# CPU_LPDDR4.net
KiCad netlist of a schematic drawn in Altium Designer
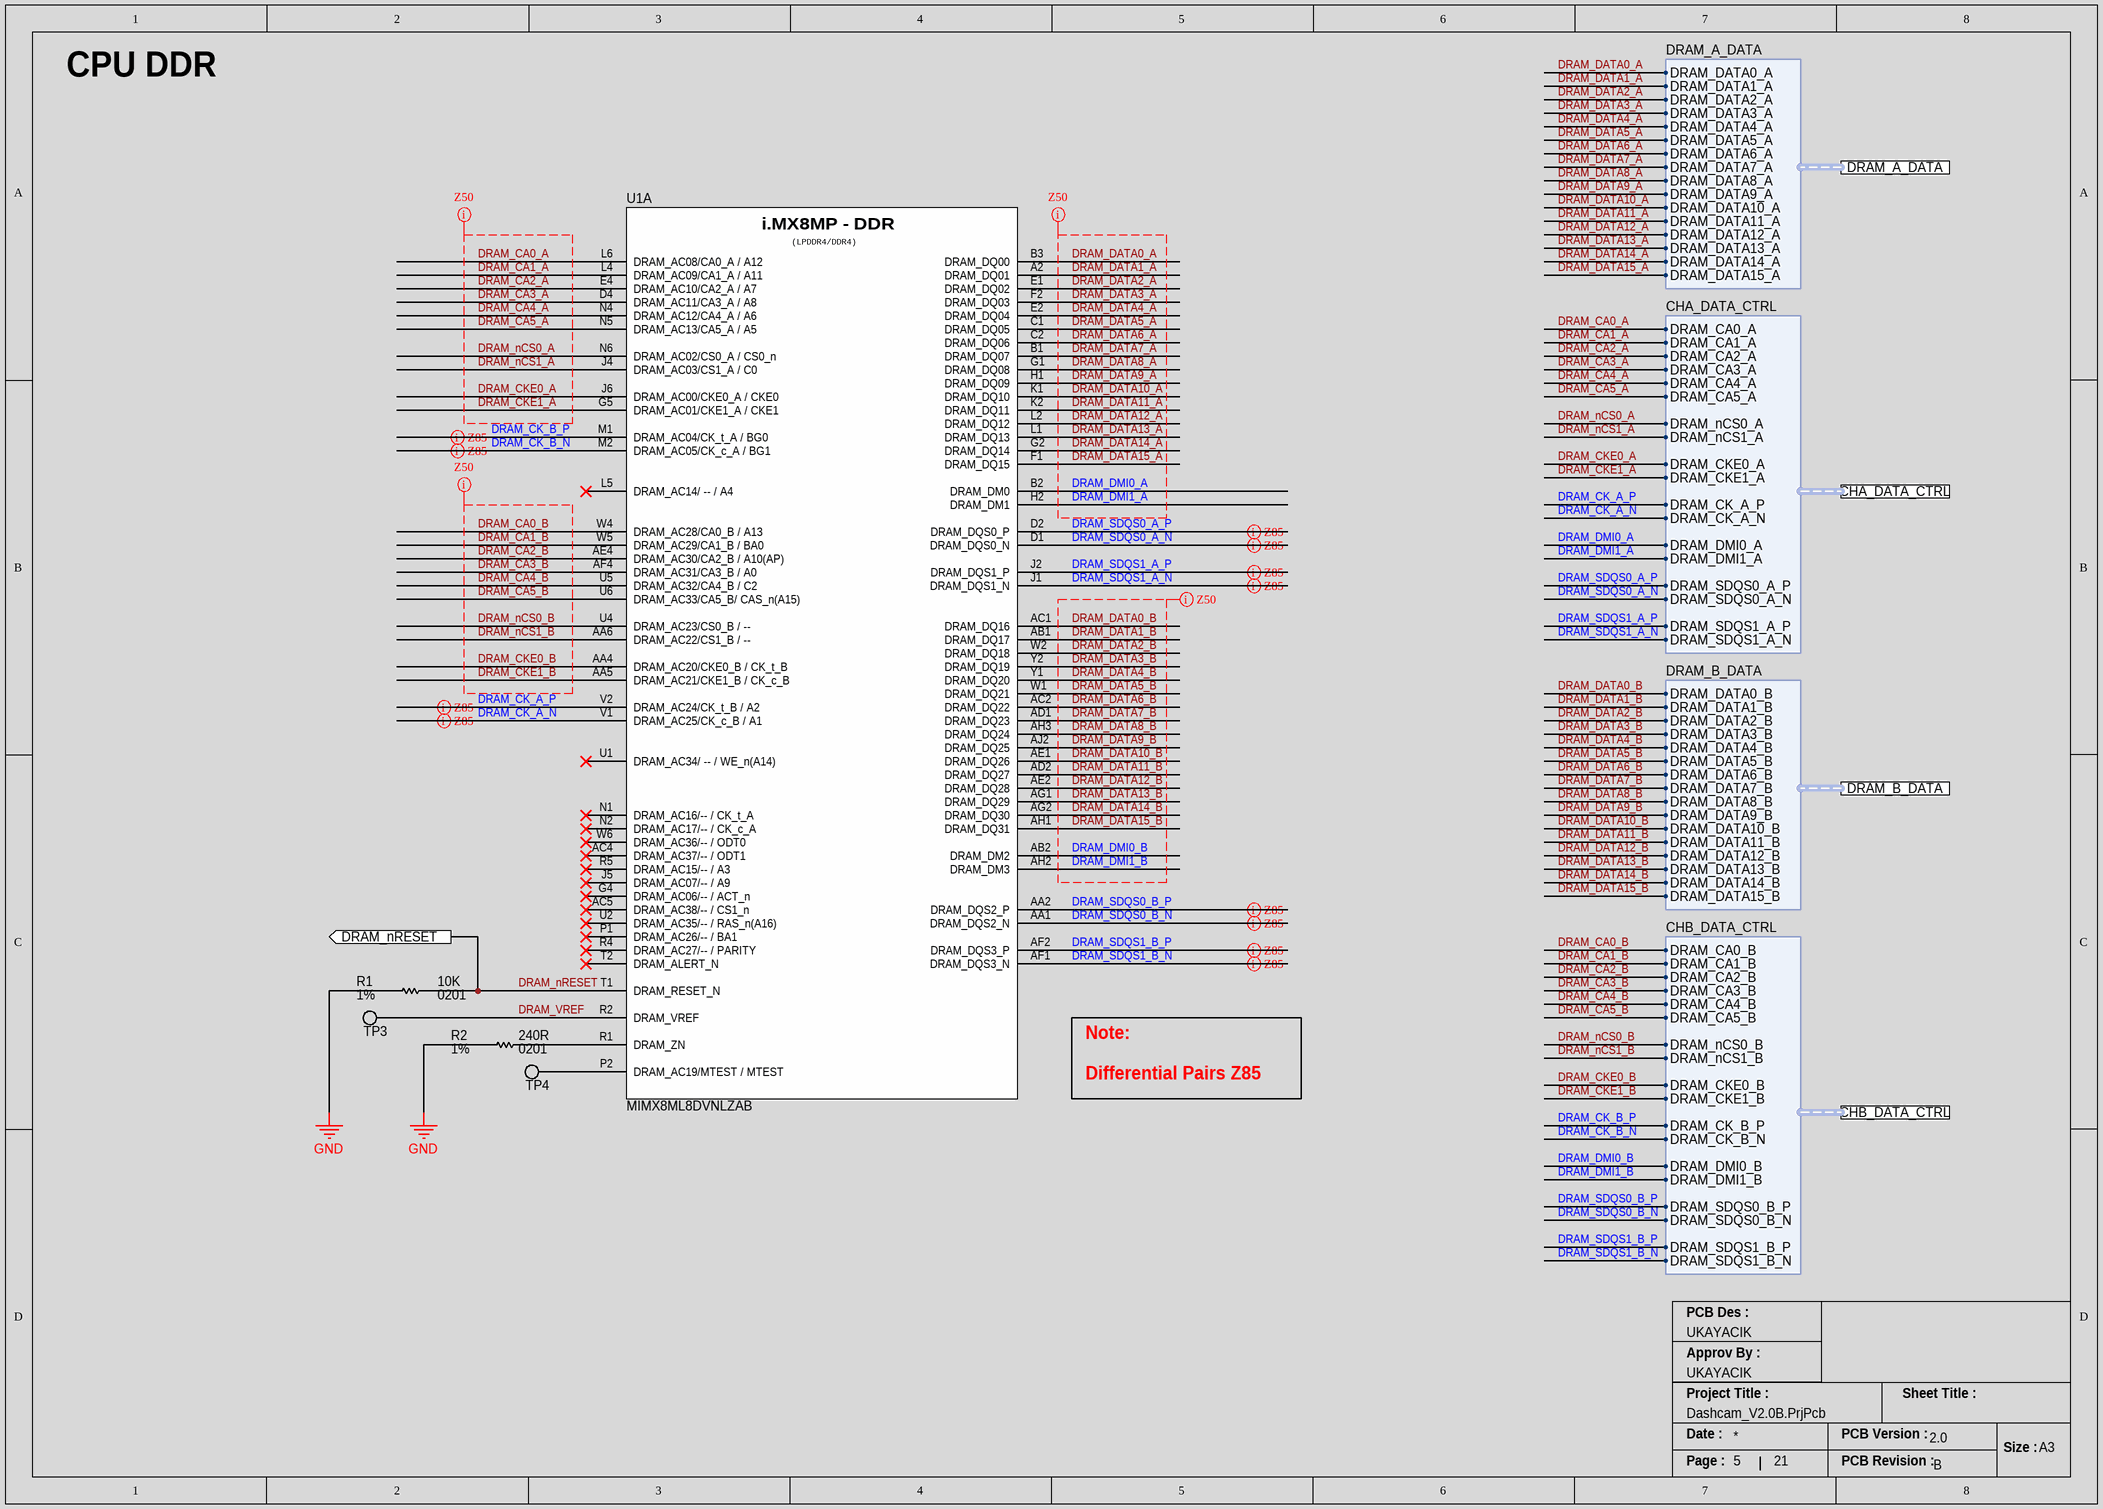
[diagram p0: CPU LPDDR4.SchDoc]

(export (version "E")
  (design (tool "Eeschema 10.0.6"))
  (components
    (comp (ref "R1")
      (value "RC0201FR-0710KL")
      (footprint "RES_0201_RESC0603X02N")
      (description "SMD Chip Resistor, 10 kOhm, ± 1%, 50 mW, 0201 [0603 Metric], Thick Film, General Purpose")
      (fields
        (field (name "MANUFACTURER") "Yageo")
        (field (name "TOLERANCE") "1%")
        (field (name "RESISTANCE") "10K")
        (field (name "CASE CODE (IMPERIAL)") "0201")
      )
      (libsource (lib "Electronic Devices_LIB") (part "RES_10K_1/12W_1%_0201"))
    )
    (comp (ref "R2")
      (value "RC0201FR-07240RL")
      (footprint "RES_0201_RESC0603X02N")
      (description "SMD Chip Resistor, 240 Ohm, ± 1%, 50 mW, 0201 [0603 Metric], Thick Film, General Purpose")
      (fields
        (field (name "MANUFACTURER") "Yageo")
        (field (name "TOLERANCE") "1%")
        (field (name "RESISTANCE") "240R")
        (field (name "CASE/PACKAGE") "0201")
      )
      (libsource (lib "Electronic Devices_LIB") (part "RES_240R_1%_50mW_0201"))
    )
    (comp (ref "TP3")
      (value "NO COMPONENT")
      (footprint "TP_PAD_0.5MM_SMD_ROUND")
      (description "Test Point, SMD pad, round, 1.5mm, 1.6mm, 3mm diameter")
      (libsource (lib "Electronic Devices_LIB") (part "TP_PAD_SMD_SMALL"))
    )
    (comp (ref "TP4")
      (value "NO COMPONENT")
      (footprint "TP_PAD_0.5MM_SMD_ROUND")
      (description "Test Point, SMD pad, round, 1.5mm, 1.6mm, 3mm diameter")
      (libsource (lib "Electronic Devices_LIB") (part "TP_PAD_SMD_SMALL"))
    )
    (comp (ref "U1")
      (value "MIMX8ML8DVNLZAB")
      (footprint "IC_MPU_BGA548C50P29X29_1500X1500X148")
      (description "i.MX 8M Plus, Consumer, / TRAY TRAY MULTIPLE DP BAKEABLE RoHS Compliant: Yes")
      (fields (field (name "MANUFACTURER") "NXP Semiconductors"))
      (libsource (lib "Electronic Devices_LIB") (part "IC_MPU_8M_PLUS_MIMX8ML8DVNLZAB"))
    )
  )
  (nets
    (net (code "5") (name "/DRAM_CA0_A") (class "Default")
      (node (ref "U1") (pin "L6") (pinfunction "DRAM_AC08/CA0_A_/_A12_L6") (pintype "passive"))
    )
    (net (code "6") (name "/DRAM_CA0_B") (class "Default")
      (node (ref "U1") (pin "W4") (pinfunction "DRAM_AC28/CA0_B_/_A13_W4") (pintype "passive"))
    )
    (net (code "7") (name "/DRAM_CA1_A") (class "Default")
      (node (ref "U1") (pin "L4") (pinfunction "DRAM_AC09/CA1_A_/_A11_L4") (pintype "passive"))
    )
    (net (code "8") (name "/DRAM_CA1_B") (class "Default")
      (node (ref "U1") (pin "W5") (pinfunction "DRAM_AC29/CA1_B_/_BA0_W5") (pintype "passive"))
    )
    (net (code "9") (name "/DRAM_CA2_A") (class "Default")
      (node (ref "U1") (pin "E4") (pinfunction "DRAM_AC10/CA2_A_/_A7_E4") (pintype "passive"))
    )
    (net (code "10") (name "/DRAM_CA2_B") (class "Default")
      (node (ref "U1") (pin "AE4") (pinfunction "DRAM_AC30/CA2_B_/_A10(AP)_AE4") (pintype "passive"))
    )
    (net (code "11") (name "/DRAM_CA3_A") (class "Default")
      (node (ref "U1") (pin "D4") (pinfunction "DRAM_AC11/CA3_A_/_A8_D4") (pintype "passive"))
    )
    (net (code "12") (name "/DRAM_CA3_B") (class "Default")
      (node (ref "U1") (pin "AF4") (pinfunction "DRAM_AC31/CA3_B_/_A0_AF4") (pintype "passive"))
    )
    (net (code "13") (name "/DRAM_CA4_A") (class "Default")
      (node (ref "U1") (pin "N4") (pinfunction "DRAM_AC12/CA4_A_/_A6_N4") (pintype "passive"))
    )
    (net (code "14") (name "/DRAM_CA4_B") (class "Default")
      (node (ref "U1") (pin "U5") (pinfunction "DRAM_AC32/CA4_B_/_C2_U5") (pintype "passive"))
    )
    (net (code "15") (name "/DRAM_CA5_A") (class "Default")
      (node (ref "U1") (pin "N5") (pinfunction "DRAM_AC13/CA5_A_/_A5_N5") (pintype "passive"))
    )
    (net (code "16") (name "/DRAM_CA5_B") (class "Default")
      (node (ref "U1") (pin "U6") (pinfunction "DRAM_AC33/CA5_B/_CAS_n(A15)_U6") (pintype "passive"))
    )
    (net (code "17") (name "/DRAM_CKE0_A") (class "Default")
      (node (ref "U1") (pin "J6") (pinfunction "DRAM_AC00/CKE0_A_/_CKE0_J6") (pintype "passive"))
    )
    (net (code "18") (name "/DRAM_CKE0_B") (class "Default")
      (node (ref "U1") (pin "AA4") (pinfunction "DRAM_AC20/CKE0_B_/_CK_t_B_AA4") (pintype "passive"))
    )
    (net (code "19") (name "/DRAM_CKE1_A") (class "Default")
      (node (ref "U1") (pin "G5") (pinfunction "DRAM_AC01/CKE1_A_/_CKE1_G5") (pintype "passive"))
    )
    (net (code "20") (name "/DRAM_CKE1_B") (class "Default")
      (node (ref "U1") (pin "AA5") (pinfunction "DRAM_AC21/CKE1_B_/_CK_c_B_AA5") (pintype "passive"))
    )
    (net (code "21") (name "/DRAM_CK_A_N") (class "Default")
      (node (ref "U1") (pin "V1") (pinfunction "DRAM_AC25/CK_c_B_/_A1_V1") (pintype "passive"))
    )
    (net (code "22") (name "/DRAM_CK_A_P") (class "Default")
      (node (ref "U1") (pin "V2") (pinfunction "DRAM_AC24/CK_t_B_/_A2_V2") (pintype "passive"))
    )
    (net (code "23") (name "/DRAM_CK_B_N") (class "Default")
      (node (ref "U1") (pin "M2") (pinfunction "DRAM_AC05/CK_c_A_/_BG1_M2") (pintype "passive"))
    )
    (net (code "24") (name "/DRAM_CK_B_P") (class "Default")
      (node (ref "U1") (pin "M1") (pinfunction "DRAM_AC04/CK_t_A_/_BG0_M1") (pintype "passive"))
    )
    (net (code "25") (name "/DRAM_DATA0_A") (class "Default")
      (node (ref "U1") (pin "B3") (pinfunction "DRAM_DQ00_B3") (pintype "passive"))
    )
    (net (code "26") (name "/DRAM_DATA0_B") (class "Default")
      (node (ref "U1") (pin "AC1") (pinfunction "DRAM_DQ16_AC1") (pintype "passive"))
    )
    (net (code "27") (name "/DRAM_DATA1_A") (class "Default")
      (node (ref "U1") (pin "A2") (pinfunction "DRAM_DQ01_A2") (pintype "passive"))
    )
    (net (code "28") (name "/DRAM_DATA1_B") (class "Default")
      (node (ref "U1") (pin "AB1") (pinfunction "DRAM_DQ17_AB1") (pintype "passive"))
    )
    (net (code "29") (name "/DRAM_DATA2_A") (class "Default")
      (node (ref "U1") (pin "E1") (pinfunction "DRAM_DQ02_E1") (pintype "passive"))
    )
    (net (code "30") (name "/DRAM_DATA2_B") (class "Default")
      (node (ref "U1") (pin "W2") (pinfunction "DRAM_DQ18_W2") (pintype "passive"))
    )
    (net (code "31") (name "/DRAM_DATA3_A") (class "Default")
      (node (ref "U1") (pin "F2") (pinfunction "DRAM_DQ03_F2") (pintype "passive"))
    )
    (net (code "32") (name "/DRAM_DATA3_B") (class "Default")
      (node (ref "U1") (pin "Y2") (pinfunction "DRAM_DQ19_Y2") (pintype "passive"))
    )
    (net (code "33") (name "/DRAM_DATA4_A") (class "Default")
      (node (ref "U1") (pin "E2") (pinfunction "DRAM_DQ04_E2") (pintype "passive"))
    )
    (net (code "34") (name "/DRAM_DATA4_B") (class "Default")
      (node (ref "U1") (pin "Y1") (pinfunction "DRAM_DQ20_Y1") (pintype "passive"))
    )
    (net (code "35") (name "/DRAM_DATA5_A") (class "Default")
      (node (ref "U1") (pin "C1") (pinfunction "DRAM_DQ05_C1") (pintype "passive"))
    )
    (net (code "36") (name "/DRAM_DATA5_B") (class "Default")
      (node (ref "U1") (pin "W1") (pinfunction "DRAM_DQ21_W1") (pintype "passive"))
    )
    (net (code "37") (name "/DRAM_DATA6_A") (class "Default")
      (node (ref "U1") (pin "C2") (pinfunction "DRAM_DQ06_C2") (pintype "passive"))
    )
    (net (code "38") (name "/DRAM_DATA6_B") (class "Default")
      (node (ref "U1") (pin "AC2") (pinfunction "DRAM_DQ22_AC2") (pintype "passive"))
    )
    (net (code "39") (name "/DRAM_DATA7_A") (class "Default")
      (node (ref "U1") (pin "B1") (pinfunction "DRAM_DQ07_B1") (pintype "passive"))
    )
    (net (code "40") (name "/DRAM_DATA7_B") (class "Default")
      (node (ref "U1") (pin "AD1") (pinfunction "DRAM_DQ23_AD1") (pintype "passive"))
    )
    (net (code "41") (name "/DRAM_DATA8_A") (class "Default")
      (node (ref "U1") (pin "G1") (pinfunction "DRAM_DQ08_G1") (pintype "passive"))
    )
    (net (code "42") (name "/DRAM_DATA8_B") (class "Default")
      (node (ref "U1") (pin "AH3") (pinfunction "DRAM_DQ24_AH3") (pintype "passive"))
    )
    (net (code "43") (name "/DRAM_DATA9_A") (class "Default")
      (node (ref "U1") (pin "H1") (pinfunction "DRAM_DQ09_H1") (pintype "passive"))
    )
    (net (code "44") (name "/DRAM_DATA9_B") (class "Default")
      (node (ref "U1") (pin "AJ2") (pinfunction "DRAM_DQ25_AJ2") (pintype "passive"))
    )
    (net (code "45") (name "/DRAM_DATA10_A") (class "Default")
      (node (ref "U1") (pin "K1") (pinfunction "DRAM_DQ10_K1") (pintype "passive"))
    )
    (net (code "46") (name "/DRAM_DATA10_B") (class "Default")
      (node (ref "U1") (pin "AE1") (pinfunction "DRAM_DQ26_AE1") (pintype "passive"))
    )
    (net (code "47") (name "/DRAM_DATA11_A") (class "Default")
      (node (ref "U1") (pin "K2") (pinfunction "DRAM_DQ11_K2") (pintype "passive"))
    )
    (net (code "48") (name "/DRAM_DATA11_B") (class "Default")
      (node (ref "U1") (pin "AD2") (pinfunction "DRAM_DQ27_AD2") (pintype "passive"))
    )
    (net (code "49") (name "/DRAM_DATA12_A") (class "Default")
      (node (ref "U1") (pin "L2") (pinfunction "DRAM_DQ12_L2") (pintype "passive"))
    )
    (net (code "50") (name "/DRAM_DATA12_B") (class "Default")
      (node (ref "U1") (pin "AE2") (pinfunction "DRAM_DQ28_AE2") (pintype "passive"))
    )
    (net (code "51") (name "/DRAM_DATA13_A") (class "Default")
      (node (ref "U1") (pin "L1") (pinfunction "DRAM_DQ13_L1") (pintype "passive"))
    )
    (net (code "52") (name "/DRAM_DATA13_B") (class "Default")
      (node (ref "U1") (pin "AG1") (pinfunction "DRAM_DQ29_AG1") (pintype "passive"))
    )
    (net (code "53") (name "/DRAM_DATA14_A") (class "Default")
      (node (ref "U1") (pin "G2") (pinfunction "DRAM_DQ14_G2") (pintype "passive"))
    )
    (net (code "54") (name "/DRAM_DATA14_B") (class "Default")
      (node (ref "U1") (pin "AG2") (pinfunction "DRAM_DQ30_AG2") (pintype "passive"))
    )
    (net (code "55") (name "/DRAM_DATA15_A") (class "Default")
      (node (ref "U1") (pin "F1") (pinfunction "DRAM_DQ15_F1") (pintype "passive"))
    )
    (net (code "56") (name "/DRAM_DATA15_B") (class "Default")
      (node (ref "U1") (pin "AH1") (pinfunction "DRAM_DQ31_AH1") (pintype "passive"))
    )
    (net (code "57") (name "/DRAM_DMI0_A") (class "Default")
      (node (ref "U1") (pin "B2") (pinfunction "DRAM_DM0_B2") (pintype "passive"))
    )
    (net (code "58") (name "/DRAM_DMI0_B") (class "Default")
      (node (ref "U1") (pin "AB2") (pinfunction "DRAM_DM2_AB2") (pintype "passive"))
    )
    (net (code "59") (name "/DRAM_DMI1_A") (class "Default")
      (node (ref "U1") (pin "H2") (pinfunction "DRAM_DM1_H2") (pintype "passive"))
    )
    (net (code "60") (name "/DRAM_DMI1_B") (class "Default")
      (node (ref "U1") (pin "AH2") (pinfunction "DRAM_DM3_AH2") (pintype "passive"))
    )
    (net (code "61") (name "/DRAM_SDQS0_A_N") (class "Default")
      (node (ref "U1") (pin "D1") (pinfunction "DRAM_DQS0_N_D1") (pintype "passive"))
    )
    (net (code "62") (name "/DRAM_SDQS0_A_P") (class "Default")
      (node (ref "U1") (pin "D2") (pinfunction "DRAM_DQS0_P_D2") (pintype "passive"))
    )
    (net (code "63") (name "/DRAM_SDQS0_B_N") (class "Default")
      (node (ref "U1") (pin "AA1") (pinfunction "DRAM_DQS2_N_AA1") (pintype "passive"))
    )
    (net (code "64") (name "/DRAM_SDQS0_B_P") (class "Default")
      (node (ref "U1") (pin "AA2") (pinfunction "DRAM_DQS2_P_AA2") (pintype "passive"))
    )
    (net (code "65") (name "/DRAM_SDQS1_A_N") (class "Default")
      (node (ref "U1") (pin "J1") (pinfunction "DRAM_DQS1_N_J1") (pintype "passive"))
    )
    (net (code "66") (name "/DRAM_SDQS1_A_P") (class "Default")
      (node (ref "U1") (pin "J2") (pinfunction "DRAM_DQS1_P_J2") (pintype "passive"))
    )
    (net (code "67") (name "/DRAM_SDQS1_B_N") (class "Default")
      (node (ref "U1") (pin "AF1") (pinfunction "DRAM_DQS3_N_AF1") (pintype "passive"))
    )
    (net (code "68") (name "/DRAM_SDQS1_B_P") (class "Default")
      (node (ref "U1") (pin "AF2") (pinfunction "DRAM_DQS3_P_AF2") (pintype "passive"))
    )
    (net (code "69") (name "/DRAM_VREF") (class "Default")
      (node (ref "TP3") (pin "1") (pinfunction "1_1") (pintype "passive"))
      (node (ref "U1") (pin "R2") (pinfunction "DRAM_VREF_R2") (pintype "passive"))
    )
    (net (code "70") (name "/DRAM_nCS0_A") (class "Default")
      (node (ref "U1") (pin "N6") (pinfunction "DRAM_AC02/CS0_A_/_CS0_n_N6") (pintype "passive"))
    )
    (net (code "71") (name "/DRAM_nCS0_B") (class "Default")
      (node (ref "U1") (pin "U4") (pinfunction "DRAM_AC23/CS0_B_/_--_U4") (pintype "passive"))
    )
    (net (code "72") (name "/DRAM_nCS1_A") (class "Default")
      (node (ref "U1") (pin "J4") (pinfunction "DRAM_AC03/CS1_A_/_C0_J4") (pintype "passive"))
    )
    (net (code "73") (name "/DRAM_nCS1_B") (class "Default")
      (node (ref "U1") (pin "AA6") (pinfunction "DRAM_AC22/CS1_B_/_--_AA6") (pintype "passive"))
    )
    (net (code "74") (name "/DRAM_nRESET") (class "Default")
      (node (ref "R1") (pin "2") (pinfunction "2_2") (pintype "passive"))
      (node (ref "U1") (pin "T1") (pinfunction "DRAM_RESET_N_T1") (pintype "passive"))
    )
    (net (code "79") (name "GND") (class "Default")
      (node (ref "R1") (pin "1") (pinfunction "1_1") (pintype "passive"))
      (node (ref "R2") (pin "1") (pinfunction "1_1") (pintype "passive"))
    )
    (net (code "80") (name "Net-(U1A-DRAM_AC19{slash}MTEST_{slash}_MTEST)") (class "Default")
      (node (ref "TP4") (pin "1") (pinfunction "1_1") (pintype "passive"))
      (node (ref "U1") (pin "P2") (pinfunction "DRAM_AC19/MTEST_/_MTEST_P2") (pintype "passive"))
    )
    (net (code "81") (name "Net-(U1A-DRAM_ZN)") (class "Default")
      (node (ref "R2") (pin "2") (pinfunction "2_2") (pintype "passive"))
      (node (ref "U1") (pin "R1") (pinfunction "DRAM_ZN_R1") (pintype "passive"))
    )
    (net (code "82") (name "unconnected-(U1A-DRAM_AC06{slash}--_{slash}_ACT_n-PadG4)") (class "Default")
      (node (ref "U1") (pin "G4") (pinfunction "DRAM_AC06/--_/_ACT_n_G4") (pintype "passive+no_connect"))
    )
    (net (code "83") (name "unconnected-(U1A-DRAM_AC07{slash}--_{slash}_A9-PadJ5)") (class "Default")
      (node (ref "U1") (pin "J5") (pinfunction "DRAM_AC07/--_/_A9_J5") (pintype "passive+no_connect"))
    )
    (net (code "84") (name "unconnected-(U1A-DRAM_AC14{slash}_--_{slash}_A4-PadL5)") (class "Default")
      (node (ref "U1") (pin "L5") (pinfunction "DRAM_AC14/_--_/_A4_L5") (pintype "passive+no_connect"))
    )
    (net (code "85") (name "unconnected-(U1A-DRAM_AC15{slash}--_{slash}_A3-PadR5)") (class "Default")
      (node (ref "U1") (pin "R5") (pinfunction "DRAM_AC15/--_/_A3_R5") (pintype "passive+no_connect"))
    )
    (net (code "86") (name "unconnected-(U1A-DRAM_AC16{slash}--_{slash}_CK_t_A-PadN1)") (class "Default")
      (node (ref "U1") (pin "N1") (pinfunction "DRAM_AC16/--_/_CK_t_A_N1") (pintype "passive+no_connect"))
    )
    (net (code "87") (name "unconnected-(U1A-DRAM_AC17{slash}--_{slash}_CK_c_A-PadN2)") (class "Default")
      (node (ref "U1") (pin "N2") (pinfunction "DRAM_AC17/--_/_CK_c_A_N2") (pintype "passive+no_connect"))
    )
    (net (code "88") (name "unconnected-(U1A-DRAM_AC26{slash}--_{slash}_BA1-PadP1)") (class "Default")
      (node (ref "U1") (pin "P1") (pinfunction "DRAM_AC26/--_/_BA1_P1") (pintype "passive+no_connect"))
    )
    (net (code "89") (name "unconnected-(U1A-DRAM_AC27{slash}--_{slash}_PARITY-PadR4)") (class "Default")
      (node (ref "U1") (pin "R4") (pinfunction "DRAM_AC27/--_/_PARITY_R4") (pintype "passive+no_connect"))
    )
    (net (code "90") (name "unconnected-(U1A-DRAM_AC34{slash}_--_{slash}_WE_n(A14)-PadU1)") (class "Default")
      (node (ref "U1") (pin "U1") (pinfunction "DRAM_AC34/_--_/_WE_n(A14)_U1") (pintype "passive+no_connect"))
    )
    (net (code "91") (name "unconnected-(U1A-DRAM_AC35{slash}--_{slash}_RAS_n(A16)-PadU2)") (class "Default")
      (node (ref "U1") (pin "U2") (pinfunction "DRAM_AC35/--_/_RAS_n(A16)_U2") (pintype "passive+no_connect"))
    )
    (net (code "92") (name "unconnected-(U1A-DRAM_AC36{slash}--_{slash}_ODT0-PadW6)") (class "Default")
      (node (ref "U1") (pin "W6") (pinfunction "DRAM_AC36/--_/_ODT0_W6") (pintype "passive+no_connect"))
    )
    (net (code "93") (name "unconnected-(U1A-DRAM_AC37{slash}--_{slash}_ODT1-PadAC4)") (class "Default")
      (node (ref "U1") (pin "AC4") (pinfunction "DRAM_AC37/--_/_ODT1_AC4") (pintype "passive+no_connect"))
    )
    (net (code "94") (name "unconnected-(U1A-DRAM_AC38{slash}--_{slash}_CS1_n-PadAC5)") (class "Default")
      (node (ref "U1") (pin "AC5") (pinfunction "DRAM_AC38/--_/_CS1_n_AC5") (pintype "passive+no_connect"))
    )
    (net (code "95") (name "unconnected-(U1A-DRAM_ALERT_N-PadT2)") (class "Default")
      (node (ref "U1") (pin "T2") (pinfunction "DRAM_ALERT_N_T2") (pintype "passive+no_connect"))
    )
  )
)
